# sheet_top.net
KiCad netlist of a schematic drawn in Altium Designer
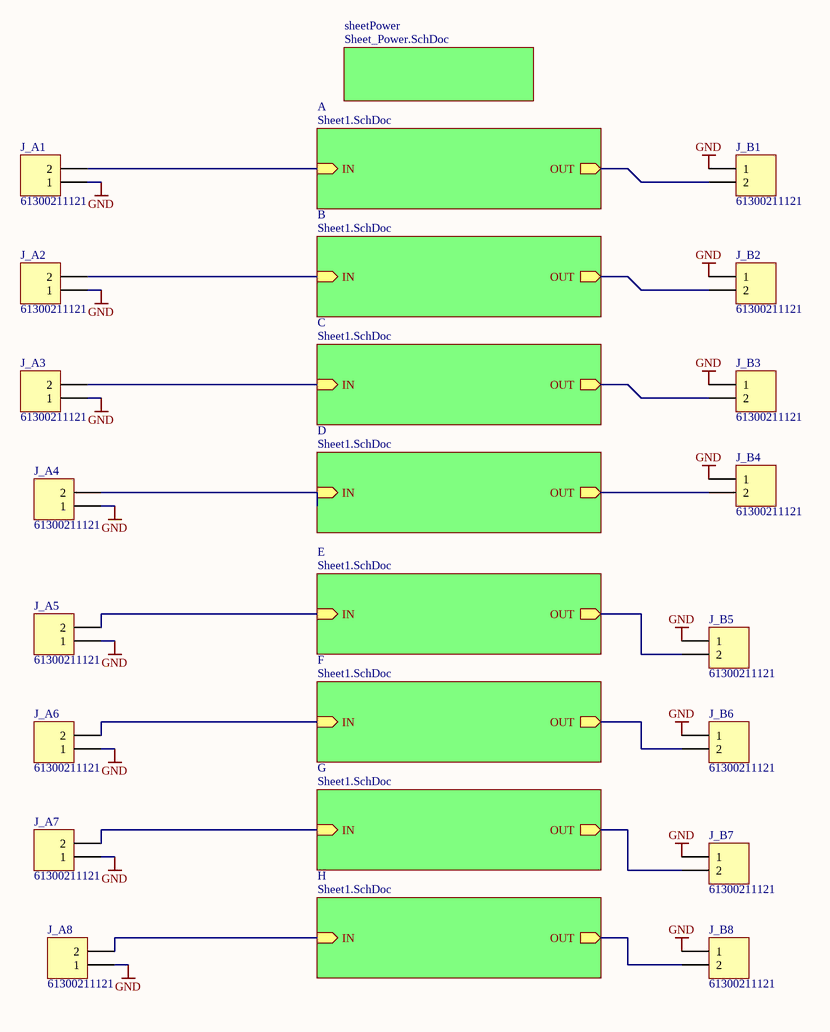
[diagram p0: sheet_top.SchDoc]

(export (version "E")
  (design (tool "Eeschema 10.0.6"))
  (components
    (comp (ref "J_A1")
      (value "61300211121")
      (footprint "61300211121")
      (description "2Pol; gerade; WR-PHD 2.54 mm THT Pin Header")
      (fields (field (name "MANUFACTURER") "Wurth Electronics"))
      (libsource (lib "") (part "CMP-001-0071-1_1"))
    )
    (comp (ref "J_A2")
      (value "61300211121")
      (footprint "61300211121")
      (description "2Pol; gerade; WR-PHD 2.54 mm THT Pin Header")
      (fields (field (name "MANUFACTURER") "Wurth Electronics"))
      (libsource (lib "") (part "CMP-001-0071-1_1"))
    )
    (comp (ref "J_A3")
      (value "61300211121")
      (footprint "61300211121")
      (description "2Pol; gerade; WR-PHD 2.54 mm THT Pin Header")
      (fields (field (name "MANUFACTURER") "Wurth Electronics"))
      (libsource (lib "") (part "CMP-001-0071-1_1"))
    )
    (comp (ref "J_A4")
      (value "61300211121")
      (footprint "61300211121")
      (description "2Pol; gerade; WR-PHD 2.54 mm THT Pin Header")
      (fields (field (name "MANUFACTURER") "Wurth Electronics"))
      (libsource (lib "") (part "CMP-001-0071-1_1"))
    )
    (comp (ref "J_A5")
      (value "61300211121")
      (footprint "61300211121")
      (description "2Pol; gerade; WR-PHD 2.54 mm THT Pin Header")
      (fields (field (name "MANUFACTURER") "Wurth Electronics"))
      (libsource (lib "") (part "CMP-001-0071-1_1"))
    )
    (comp (ref "J_A6")
      (value "61300211121")
      (footprint "61300211121")
      (description "2Pol; gerade; WR-PHD 2.54 mm THT Pin Header")
      (fields (field (name "MANUFACTURER") "Wurth Electronics"))
      (libsource (lib "") (part "CMP-001-0071-1_1"))
    )
    (comp (ref "J_A7")
      (value "61300211121")
      (footprint "61300211121")
      (description "2Pol; gerade; WR-PHD 2.54 mm THT Pin Header")
      (fields (field (name "MANUFACTURER") "Wurth Electronics"))
      (libsource (lib "") (part "CMP-001-0071-1_1"))
    )
    (comp (ref "J_A8")
      (value "61300211121")
      (footprint "61300211121")
      (description "2Pol; gerade; WR-PHD 2.54 mm THT Pin Header")
      (fields (field (name "MANUFACTURER") "Wurth Electronics"))
      (libsource (lib "") (part "CMP-001-0071-1_1"))
    )
    (comp (ref "J_B1")
      (value "61300211121")
      (footprint "61300211121")
      (description "2Pol; gerade; WR-PHD 2.54 mm THT Pin Header")
      (fields (field (name "MANUFACTURER") "Wurth Electronics"))
      (libsource (lib "Altium Vault EMBL 3") (part "61300211121"))
    )
    (comp (ref "J_B2")
      (value "61300211121")
      (footprint "61300211121")
      (description "2Pol; gerade; WR-PHD 2.54 mm THT Pin Header")
      (fields (field (name "MANUFACTURER") "Wurth Electronics"))
      (libsource (lib "Altium Vault EMBL 3") (part "CMP-001-0071-1"))
    )
    (comp (ref "J_B3")
      (value "61300211121")
      (footprint "61300211121")
      (description "2Pol; gerade; WR-PHD 2.54 mm THT Pin Header")
      (fields (field (name "MANUFACTURER") "Wurth Electronics"))
      (libsource (lib "Altium Vault EMBL 3") (part "CMP-001-0071-1"))
    )
    (comp (ref "J_B4")
      (value "61300211121")
      (footprint "61300211121")
      (description "2Pol; gerade; WR-PHD 2.54 mm THT Pin Header")
      (fields (field (name "MANUFACTURER") "Wurth Electronics"))
      (libsource (lib "Altium Vault EMBL 3") (part "CMP-001-0071-1"))
    )
    (comp (ref "J_B5")
      (value "61300211121")
      (footprint "61300211121")
      (description "2Pol; gerade; WR-PHD 2.54 mm THT Pin Header")
      (fields (field (name "MANUFACTURER") "Wurth Electronics"))
      (libsource (lib "Altium Vault EMBL 3") (part "CMP-001-0071-1"))
    )
    (comp (ref "J_B6")
      (value "61300211121")
      (footprint "61300211121")
      (description "2Pol; gerade; WR-PHD 2.54 mm THT Pin Header")
      (fields (field (name "MANUFACTURER") "Wurth Electronics"))
      (libsource (lib "Altium Vault EMBL 3") (part "CMP-001-0071-1"))
    )
    (comp (ref "J_B7")
      (value "61300211121")
      (footprint "61300211121")
      (description "2Pol; gerade; WR-PHD 2.54 mm THT Pin Header")
      (fields (field (name "MANUFACTURER") "Wurth Electronics"))
      (libsource (lib "Altium Vault EMBL 3") (part "CMP-001-0071-1"))
    )
    (comp (ref "J_B8")
      (value "61300211121")
      (footprint "61300211121")
      (description "2Pol; gerade; WR-PHD 2.54 mm THT Pin Header")
      (fields (field (name "MANUFACTURER") "Wurth Electronics"))
      (libsource (lib "Altium Vault EMBL 3") (part "CMP-001-0071-1"))
    )
  )
  (nets
    (net (code "1") (name "/IN") (class "Default")
      (node (ref "J_A8") (pin "2") (pinfunction "2_2") (pintype "passive"))
    )
    (net (code "2") (name "/IN_1") (class "Default")
      (node (ref "J_A1") (pin "2") (pinfunction "2_2") (pintype "passive"))
    )
    (net (code "3") (name "/IN_2") (class "Default")
      (node (ref "J_A2") (pin "2") (pinfunction "2_2") (pintype "passive"))
    )
    (net (code "4") (name "/IN_3") (class "Default")
      (node (ref "J_A3") (pin "2") (pinfunction "2_2") (pintype "passive"))
    )
    (net (code "5") (name "/IN_4") (class "Default")
      (node (ref "J_A4") (pin "2") (pinfunction "2_2") (pintype "passive"))
    )
    (net (code "6") (name "/IN_5") (class "Default")
      (node (ref "J_A5") (pin "2") (pinfunction "2_2") (pintype "passive"))
    )
    (net (code "7") (name "/IN_6") (class "Default")
      (node (ref "J_A6") (pin "2") (pinfunction "2_2") (pintype "passive"))
    )
    (net (code "8") (name "/IN_7") (class "Default")
      (node (ref "J_A7") (pin "2") (pinfunction "2_2") (pintype "passive"))
    )
    (net (code "9") (name "/OUT") (class "Default")
      (node (ref "J_B3") (pin "2") (pinfunction "2_2") (pintype "passive"))
    )
    (net (code "10") (name "/OUT_1") (class "Default")
      (node (ref "J_B8") (pin "2") (pinfunction "2_2") (pintype "passive"))
    )
    (net (code "11") (name "/OUT_2") (class "Default")
      (node (ref "J_B4") (pin "2") (pinfunction "2_2") (pintype "passive"))
    )
    (net (code "12") (name "/OUT_3") (class "Default")
      (node (ref "J_B5") (pin "2") (pinfunction "2_2") (pintype "passive"))
    )
    (net (code "13") (name "/OUT_4") (class "Default")
      (node (ref "J_B1") (pin "2") (pinfunction "2_2") (pintype "passive"))
    )
    (net (code "14") (name "/OUT_5") (class "Default")
      (node (ref "J_B2") (pin "2") (pinfunction "2_2") (pintype "passive"))
    )
    (net (code "15") (name "/OUT_6") (class "Default")
      (node (ref "J_B6") (pin "2") (pinfunction "2_2") (pintype "passive"))
    )
    (net (code "16") (name "/OUT_7") (class "Default")
      (node (ref "J_B7") (pin "2") (pinfunction "2_2") (pintype "passive"))
    )
    (net (code "17") (name "GND") (class "Default")
      (node (ref "J_A1") (pin "1") (pinfunction "1_1") (pintype "passive"))
      (node (ref "J_A2") (pin "1") (pinfunction "1_1") (pintype "passive"))
      (node (ref "J_A3") (pin "1") (pinfunction "1_1") (pintype "passive"))
      (node (ref "J_A4") (pin "1") (pinfunction "1_1") (pintype "passive"))
      (node (ref "J_A5") (pin "1") (pinfunction "1_1") (pintype "passive"))
      (node (ref "J_A6") (pin "1") (pinfunction "1_1") (pintype "passive"))
      (node (ref "J_A7") (pin "1") (pinfunction "1_1") (pintype "passive"))
      (node (ref "J_A8") (pin "1") (pinfunction "1_1") (pintype "passive"))
      (node (ref "J_B1") (pin "1") (pinfunction "1_1") (pintype "passive"))
      (node (ref "J_B2") (pin "1") (pinfunction "1_1") (pintype "passive"))
      (node (ref "J_B3") (pin "1") (pinfunction "1_1") (pintype "passive"))
      (node (ref "J_B4") (pin "1") (pinfunction "1_1") (pintype "passive"))
      (node (ref "J_B5") (pin "1") (pinfunction "1_1") (pintype "passive"))
      (node (ref "J_B6") (pin "1") (pinfunction "1_1") (pintype "passive"))
      (node (ref "J_B7") (pin "1") (pinfunction "1_1") (pintype "passive"))
      (node (ref "J_B8") (pin "1") (pinfunction "1_1") (pintype "passive"))
    )
  )
)
